# Puca1.net
KiCad netlist of a schematic drawn in Altium Designer
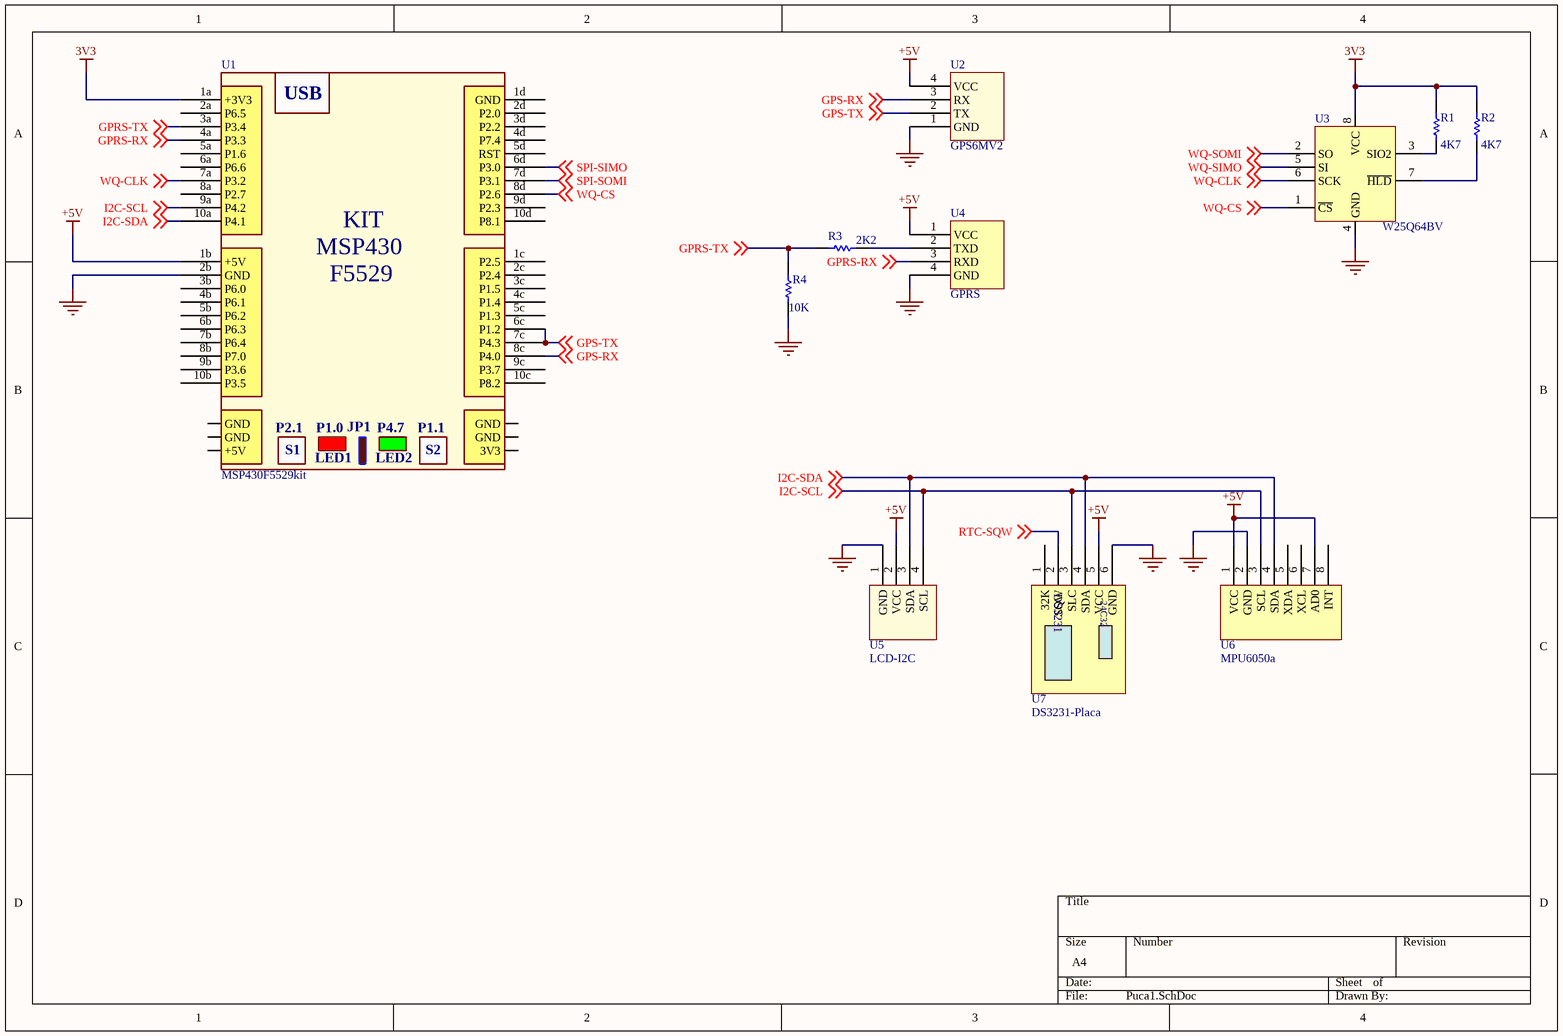
[diagram p0: Puca1.SchDoc]

(export (version "E")
  (design (tool "Eeschema 10.0.6"))
  (components
    (comp (ref "R1")
      (value "4K7")
      (footprint "AXIAL-0.3")
      (description "Resistor")
      (fields (field (name "Comment") "Res1") (field (name "PUBLISHER") "Altium Limited"))
      (libsource (lib "Miscellaneous Devices") (part "Res1"))
    )
    (comp (ref "R2")
      (value "4K7")
      (footprint "AXIAL-0.3")
      (description "Resistor")
      (fields (field (name "Comment") "Res1") (field (name "PUBLISHER") "Altium Limited"))
      (libsource (lib "Miscellaneous Devices") (part "Res1"))
    )
    (comp (ref "R3")
      (value "2K2")
      (footprint "AXIAL-0.3")
      (description "Resistor")
      (fields (field (name "Comment") "Res1") (field (name "PUBLISHER") "Altium Limited"))
      (libsource (lib "Miscellaneous Devices") (part "Res1"))
    )
    (comp (ref "R4")
      (value "10K")
      (footprint "AXIAL-0.3")
      (description "Resistor")
      (fields (field (name "Comment") "Res1") (field (name "PUBLISHER") "Altium Limited"))
      (libsource (lib "Miscellaneous Devices") (part "Res1"))
    )
    (comp (ref "U1") (value "MSP430F5529kit") (libsource (lib "Zele_Sch") (part "MSP430F5529kit")))
    (comp (ref "U2") (value "GPS6MV2") (libsource (lib "Zele_Sch") (part "GPS6MV2")))
    (comp (ref "U3")
      (value "W25Q64BV")
      (description "FLASH 8MB")
      (libsource (lib "Zele_Sch") (part "W25Q64BV"))
    )
    (comp (ref "U4") (value "GPRS") (libsource (lib "Zele_Sch") (part "GPRS")))
    (comp (ref "U5") (value "LCD-I2C") (libsource (lib "Zele_Sch") (part "LCD-I2C")))
    (comp (ref "U6") (value "MPU6050a") (libsource (lib "Zele_Sch") (part "MPU6050a")))
    (comp (ref "U7") (value "DS3231-Placa") (libsource (lib "Zele_Sch") (part "DS3231-Placa")))
  )
  (nets
    (net (code "1") (name "+5V") (class "Default")
      (node (ref "U1") (pin "1b") (pinfunction "+5V_1b") (pintype "passive"))
      (node (ref "U2") (pin "4") (pinfunction "VCC_4") (pintype "passive"))
      (node (ref "U4") (pin "1") (pinfunction "VCC_1") (pintype "passive"))
      (node (ref "U5") (pin "2") (pinfunction "VCC_2") (pintype "passive"))
      (node (ref "U6") (pin "1") (pinfunction "VCC_1") (pintype "passive"))
      (node (ref "U6") (pin "7") (pinfunction "AD0_7") (pintype "passive"))
      (node (ref "U7") (pin "5") (pinfunction "VCC_5") (pintype "passive"))
    )
    (net (code "2") (name "3V3") (class "Default")
      (node (ref "R1") (pin "1") (pinfunction "1_1") (pintype "passive"))
      (node (ref "R2") (pin "2") (pinfunction "2_2") (pintype "passive"))
      (node (ref "U1") (pin "1a") (pinfunction "+3V3_1a") (pintype "passive"))
      (node (ref "U3") (pin "8") (pinfunction "VCC_8") (pintype "power_in"))
    )
    (net (code "3") (name "<NO NET>") (class "Default")
      (node (ref "R4") (pin "2") (pinfunction "2_2") (pintype "passive"))
      (node (ref "U1") (pin "2b") (pinfunction "GND_2b") (pintype "passive"))
      (node (ref "U2") (pin "1") (pinfunction "GND_1") (pintype "passive"))
      (node (ref "U3") (pin "4") (pinfunction "GND_4") (pintype "power_in"))
      (node (ref "U4") (pin "4") (pinfunction "GND_4") (pintype "passive"))
      (node (ref "U5") (pin "1") (pinfunction "GND_1") (pintype "passive"))
      (node (ref "U6") (pin "2") (pinfunction "GND_2") (pintype "passive"))
      (node (ref "U7") (pin "6") (pinfunction "GND_6") (pintype "passive"))
    )
    (net (code "4") (name "GPRS-RX") (class "Default")
      (node (ref "U1") (pin "4a") (pinfunction "P3.3_4a") (pintype "passive"))
      (node (ref "U4") (pin "3") (pinfunction "RXD_3") (pintype "passive"))
    )
    (net (code "5") (name "GPRS-TX") (class "Default")
      (node (ref "R3") (pin "2") (pinfunction "2_2") (pintype "passive"))
      (node (ref "R4") (pin "1") (pinfunction "1_1") (pintype "passive"))
      (node (ref "U1") (pin "3a") (pinfunction "P3.4_3a") (pintype "passive"))
    )
    (net (code "6") (name "GPS-RX") (class "Default")
      (node (ref "U1") (pin "8c") (pinfunction "P4.0_8c") (pintype "passive"))
      (node (ref "U2") (pin "3") (pinfunction "RX_3") (pintype "passive"))
    )
    (net (code "7") (name "GPS-TX") (class "Default")
      (node (ref "U1") (pin "6c") (pinfunction "P1.2_6c") (pintype "passive"))
      (node (ref "U1") (pin "7c") (pinfunction "P4.3_7c") (pintype "passive"))
      (node (ref "U2") (pin "2") (pinfunction "TX_2") (pintype "passive"))
    )
    (net (code "8") (name "I2C-SCL") (class "Default")
      (node (ref "U1") (pin "9a") (pinfunction "P4.2_9a") (pintype "passive"))
      (node (ref "U5") (pin "4") (pinfunction "SCL_4") (pintype "passive"))
      (node (ref "U6") (pin "3") (pinfunction "SCL_3") (pintype "passive"))
      (node (ref "U7") (pin "3") (pinfunction "SLC_3") (pintype "passive"))
    )
    (net (code "9") (name "I2C-SDA") (class "Default")
      (node (ref "U1") (pin "10a") (pinfunction "P4.1_10a") (pintype "passive"))
      (node (ref "U5") (pin "3") (pinfunction "SDA_3") (pintype "passive"))
      (node (ref "U6") (pin "4") (pinfunction "SDA_4") (pintype "passive"))
      (node (ref "U7") (pin "4") (pinfunction "SDA_4") (pintype "passive"))
    )
    (net (code "10") (name "Net-(U3-SIO2)") (class "Default")
      (node (ref "R1") (pin "2") (pinfunction "2_2") (pintype "passive"))
      (node (ref "U3") (pin "3") (pinfunction "SIO2_3") (pintype "passive"))
    )
    (net (code "11") (name "Net-(U3-~{HLD})") (class "Default")
      (node (ref "R2") (pin "1") (pinfunction "1_1") (pintype "passive"))
      (node (ref "U3") (pin "7") (pinfunction "~{HLD}_7") (pintype "passive"))
    )
    (net (code "12") (name "Net-(U4-TXD)") (class "Default")
      (node (ref "R3") (pin "1") (pinfunction "1_1") (pintype "passive"))
      (node (ref "U4") (pin "2") (pinfunction "TXD_2") (pintype "passive"))
    )
    (net (code "13") (name "RTC-SQW") (class "Default")
      (node (ref "U7") (pin "2") (pinfunction "SQW_2") (pintype "passive"))
    )
    (net (code "14") (name "SPI-SIMO") (class "Default")
      (node (ref "U1") (pin "6d") (pinfunction "P3.0_6d") (pintype "passive"))
    )
    (net (code "15") (name "SPI-SOMI") (class "Default")
      (node (ref "U1") (pin "7d") (pinfunction "P3.1_7d") (pintype "passive"))
    )
    (net (code "16") (name "WQ-CLK") (class "Default")
      (node (ref "U1") (pin "7a") (pinfunction "P3.2_7a") (pintype "passive"))
      (node (ref "U3") (pin "6") (pinfunction "SCK_6") (pintype "passive"))
    )
    (net (code "17") (name "WQ-CS") (class "Default")
      (node (ref "U1") (pin "8d") (pinfunction "P2.6_8d") (pintype "passive"))
      (node (ref "U3") (pin "1") (pinfunction "~{CS}_1") (pintype "passive"))
    )
    (net (code "18") (name "WQ-SIMO") (class "Default")
      (node (ref "U3") (pin "5") (pinfunction "SI_5") (pintype "passive"))
    )
    (net (code "19") (name "WQ-SOMI") (class "Default")
      (node (ref "U3") (pin "2") (pinfunction "SO_2") (pintype "passive"))
    )
    (net (code "20") (name "unconnected-(U1-GND-Pad1d)") (class "Default")
      (node (ref "U1") (pin "1d") (pinfunction "GND_1d") (pintype "passive"))
    )
    (net (code "21") (name "unconnected-(U1-P1.3-Pad5c)") (class "Default")
      (node (ref "U1") (pin "5c") (pinfunction "P1.3_5c") (pintype "passive"))
    )
    (net (code "22") (name "unconnected-(U1-P1.4-Pad4c)") (class "Default")
      (node (ref "U1") (pin "4c") (pinfunction "P1.4_4c") (pintype "passive"))
    )
    (net (code "23") (name "unconnected-(U1-P1.5-Pad3c)") (class "Default")
      (node (ref "U1") (pin "3c") (pinfunction "P1.5_3c") (pintype "passive"))
    )
    (net (code "24") (name "unconnected-(U1-P1.6-Pad5a)") (class "Default")
      (node (ref "U1") (pin "5a") (pinfunction "P1.6_5a") (pintype "passive"))
    )
    (net (code "25") (name "unconnected-(U1-P2.0-Pad2d)") (class "Default")
      (node (ref "U1") (pin "2d") (pinfunction "P2.0_2d") (pintype "passive"))
    )
    (net (code "26") (name "unconnected-(U1-P2.2-Pad3d)") (class "Default")
      (node (ref "U1") (pin "3d") (pinfunction "P2.2_3d") (pintype "passive"))
    )
    (net (code "27") (name "unconnected-(U1-P2.3-Pad9d)") (class "Default")
      (node (ref "U1") (pin "9d") (pinfunction "P2.3_9d") (pintype "passive"))
    )
    (net (code "28") (name "unconnected-(U1-P2.4-Pad2c)") (class "Default")
      (node (ref "U1") (pin "2c") (pinfunction "P2.4_2c") (pintype "passive"))
    )
    (net (code "29") (name "unconnected-(U1-P2.5-Pad1c)") (class "Default")
      (node (ref "U1") (pin "1c") (pinfunction "P2.5_1c") (pintype "passive"))
    )
    (net (code "30") (name "unconnected-(U1-P2.7-Pad8a)") (class "Default")
      (node (ref "U1") (pin "8a") (pinfunction "P2.7_8a") (pintype "passive"))
    )
    (net (code "31") (name "unconnected-(U1-P3.5-Pad10b)") (class "Default")
      (node (ref "U1") (pin "10b") (pinfunction "P3.5_10b") (pintype "passive"))
    )
    (net (code "32") (name "unconnected-(U1-P3.6-Pad9b)") (class "Default")
      (node (ref "U1") (pin "9b") (pinfunction "P3.6_9b") (pintype "passive"))
    )
    (net (code "33") (name "unconnected-(U1-P3.7-Pad9c)") (class "Default")
      (node (ref "U1") (pin "9c") (pinfunction "P3.7_9c") (pintype "passive"))
    )
    (net (code "34") (name "unconnected-(U1-P6.0-Pad3b)") (class "Default")
      (node (ref "U1") (pin "3b") (pinfunction "P6.0_3b") (pintype "passive"))
    )
    (net (code "35") (name "unconnected-(U1-P6.1-Pad4b)") (class "Default")
      (node (ref "U1") (pin "4b") (pinfunction "P6.1_4b") (pintype "passive"))
    )
    (net (code "36") (name "unconnected-(U1-P6.2-Pad5b)") (class "Default")
      (node (ref "U1") (pin "5b") (pinfunction "P6.2_5b") (pintype "passive"))
    )
    (net (code "37") (name "unconnected-(U1-P6.3-Pad6b)") (class "Default")
      (node (ref "U1") (pin "6b") (pinfunction "P6.3_6b") (pintype "passive"))
    )
    (net (code "38") (name "unconnected-(U1-P6.4-Pad7b)") (class "Default")
      (node (ref "U1") (pin "7b") (pinfunction "P6.4_7b") (pintype "passive"))
    )
    (net (code "39") (name "unconnected-(U1-P6.5-Pad2a)") (class "Default")
      (node (ref "U1") (pin "2a") (pinfunction "P6.5_2a") (pintype "passive"))
    )
    (net (code "40") (name "unconnected-(U1-P6.6-Pad6a)") (class "Default")
      (node (ref "U1") (pin "6a") (pinfunction "P6.6_6a") (pintype "passive"))
    )
    (net (code "41") (name "unconnected-(U1-P7.0-Pad8b)") (class "Default")
      (node (ref "U1") (pin "8b") (pinfunction "P7.0_8b") (pintype "passive"))
    )
    (net (code "42") (name "unconnected-(U1-P7.4-Pad4d)") (class "Default")
      (node (ref "U1") (pin "4d") (pinfunction "P7.4_4d") (pintype "passive"))
    )
    (net (code "43") (name "unconnected-(U1-P8.1-Pad10d)") (class "Default")
      (node (ref "U1") (pin "10d") (pinfunction "P8.1_10d") (pintype "passive"))
    )
    (net (code "44") (name "unconnected-(U1-P8.2-Pad10c)") (class "Default")
      (node (ref "U1") (pin "10c") (pinfunction "P8.2_10c") (pintype "passive"))
    )
    (net (code "45") (name "unconnected-(U1-Pad+5V)") (class "Default")
      (node (ref "U1") (pin "+5V") (pinfunction "+5V_+5V") (pintype "passive"))
    )
    (net (code "46") (name "unconnected-(U1-Pad3V3)") (class "Default")
      (node (ref "U1") (pin "3V3") (pinfunction "3V3_3V3") (pintype "passive"))
    )
    (net (code "47") (name "unconnected-(U1-PadGND)") (class "Default")
      (node (ref "U1") (pin "GND") (pinfunction "GND_GND") (pintype "passive"))
    )
    (net (code "48") (name "unconnected-(U1-PadGND)_1") (class "Default")
      (node (ref "U1") (pin "GND") (pinfunction "GND_GND") (pintype "passive"))
    )
    (net (code "49") (name "unconnected-(U1-PadGND)_2") (class "Default")
      (node (ref "U1") (pin "GND") (pinfunction "GND_GND") (pintype "passive"))
    )
    (net (code "50") (name "unconnected-(U1-PadGND)_3") (class "Default")
      (node (ref "U1") (pin "GND") (pinfunction "GND_GND") (pintype "passive"))
    )
    (net (code "51") (name "unconnected-(U1-RST-Pad5d)") (class "Default")
      (node (ref "U1") (pin "5d") (pinfunction "RST_5d") (pintype "passive"))
    )
    (net (code "52") (name "unconnected-(U6-INT-Pad8)") (class "Default")
      (node (ref "U6") (pin "8") (pinfunction "INT_8") (pintype "passive"))
    )
    (net (code "53") (name "unconnected-(U6-XCL-Pad6)") (class "Default")
      (node (ref "U6") (pin "6") (pinfunction "XCL_6") (pintype "passive"))
    )
    (net (code "54") (name "unconnected-(U6-XDA-Pad5)") (class "Default")
      (node (ref "U6") (pin "5") (pinfunction "XDA_5") (pintype "passive"))
    )
    (net (code "55") (name "unconnected-(U7-32K-Pad1)") (class "Default")
      (node (ref "U7") (pin "1") (pinfunction "32K_1") (pintype "passive"))
    )
  )
)
